# Computer_Power_Relay_-_Power_Strip.net
KiCad netlist of a schematic drawn in EAGLE
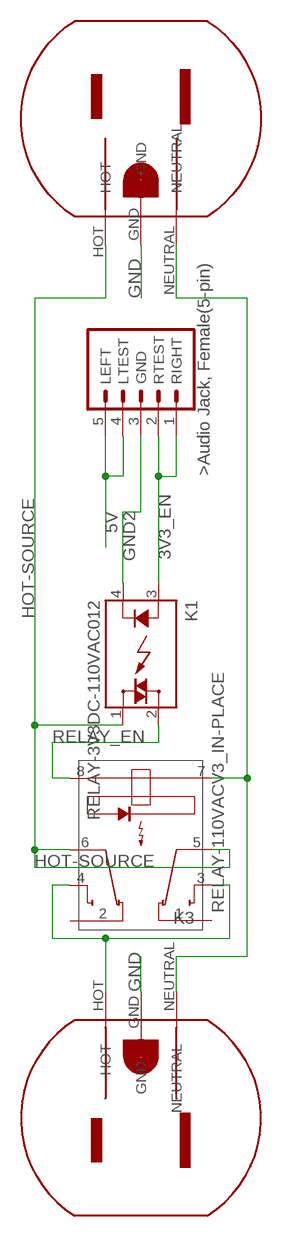
[diagram p0: schematic, sheet 1]

(export (version "E")
  (design (tool "Eeschema 10.0.6"))
  (components
    (comp (ref "K1")
      (value "RELAY-3V3DC-110VAC012")
      (footprint "eagle-import:RELAY-3V3-110V")
      (fields (field (name "MPN") "ACV33012"))
      (libsource (lib "eagle-import") (part "RELAY-3V3DC-110VAC012"))
    )
    (comp (ref "K3")
      (value "RELAY-110VACV3_IN-PLACE")
      (footprint "eagle-import:RELAY-110VAC-V3")
      (libsource (lib "eagle-import") (part "RELAY-110VACV3_IN-PLACE"))
    )
    (comp (ref "U$1")
      (value "AUDIO_JACK_FEMALE_5-PIN")
      (footprint "eagle-import:AUDIO_JACK_FEMALE_5-PIN")
      (libsource (lib "eagle-import") (part "AUDIO_JACK_FEMALE_5-PIN"))
    )
    (comp (ref "U$2")
      (value "MAINS-POWER-OUTLET3-PIN")
      (footprint "eagle-import:3-PIN-POWER")
      (libsource (lib "eagle-import") (part "MAINS-POWER-OUTLET3-PIN"))
    )
    (comp (ref "U$3")
      (value "MAINS-POWER-OUTLET3-PIN")
      (footprint "eagle-import:3-PIN-POWER")
      (libsource (lib "eagle-import") (part "MAINS-POWER-OUTLET3-PIN"))
    )
  )
  (nets
    (net (code "1") (name "/3V3_EN") (class "Default")
      (node (ref "K1") (pin "3") (pinfunction "3_3") (pintype "passive"))
      (node (ref "U$1") (pin "1") (pinfunction "RIGHT_1") (pintype "input"))
      (node (ref "U$1") (pin "2") (pinfunction "RTEST_2") (pintype "output"))
    )
    (net (code "2") (name "/5V") (class "Default")
      (node (ref "U$1") (pin "4") (pinfunction "LTEST_4") (pintype "output"))
      (node (ref "U$1") (pin "5") (pinfunction "LEFT_5") (pintype "input"))
    )
    (net (code "3") (name "/GND") (class "Default")
      (node (ref "U$2") (pin "GND") (pinfunction "GND_GND") (pintype "bidirectional"))
      (node (ref "U$3") (pin "GND") (pinfunction "GND_GND") (pintype "bidirectional"))
    )
    (net (code "4") (name "/GND2") (class "Default")
      (node (ref "K1") (pin "4") (pinfunction "4_4") (pintype "passive"))
      (node (ref "U$1") (pin "3") (pinfunction "GND_3") (pintype "power_in"))
    )
    (net (code "5") (name "/HOT-SOURCE") (class "Default")
      (node (ref "K1") (pin "1") (pinfunction "1_1") (pintype "passive"))
      (node (ref "K3") (pin "5") (pinfunction "5_5") (pintype "bidirectional"))
      (node (ref "K3") (pin "6") (pinfunction "6_6") (pintype "bidirectional"))
      (node (ref "U$3") (pin "HOT") (pinfunction "HOT_HOT") (pintype "bidirectional"))
    )
    (net (code "6") (name "/RELAY_EN") (class "Default")
      (node (ref "K1") (pin "2") (pinfunction "2_2") (pintype "passive"))
      (node (ref "K3") (pin "8") (pinfunction "8_8") (pintype "passive"))
    )
    (net (code "7") (name "Net-(K3-Pad3)") (class "Default")
      (node (ref "K3") (pin "3") (pinfunction "3_3") (pintype "bidirectional"))
      (node (ref "K3") (pin "4") (pinfunction "4_4") (pintype "bidirectional"))
      (node (ref "U$2") (pin "HOT") (pinfunction "HOT_HOT") (pintype "bidirectional"))
    )
    (net (code "8") (name "Net-(K3-Pad7)") (class "Default")
      (node (ref "K3") (pin "7") (pinfunction "7_7") (pintype "passive"))
      (node (ref "U$2") (pin "NEUTRAL") (pinfunction "NEUTRAL_NEUTRAL") (pintype "bidirectional"))
      (node (ref "U$3") (pin "NEUTRAL") (pinfunction "NEUTRAL_NEUTRAL") (pintype "bidirectional"))
    )
    (net (code "9") (name "unconnected-(K3-Pad1)") (class "Default")
      (node (ref "K3") (pin "1") (pinfunction "1_1") (pintype "bidirectional"))
    )
    (net (code "10") (name "unconnected-(K3-Pad2)") (class "Default")
      (node (ref "K3") (pin "2") (pinfunction "2_2") (pintype "bidirectional"))
    )
  )
)
